# LNA.net
KiCad netlist of a schematic drawn in Altium Designer
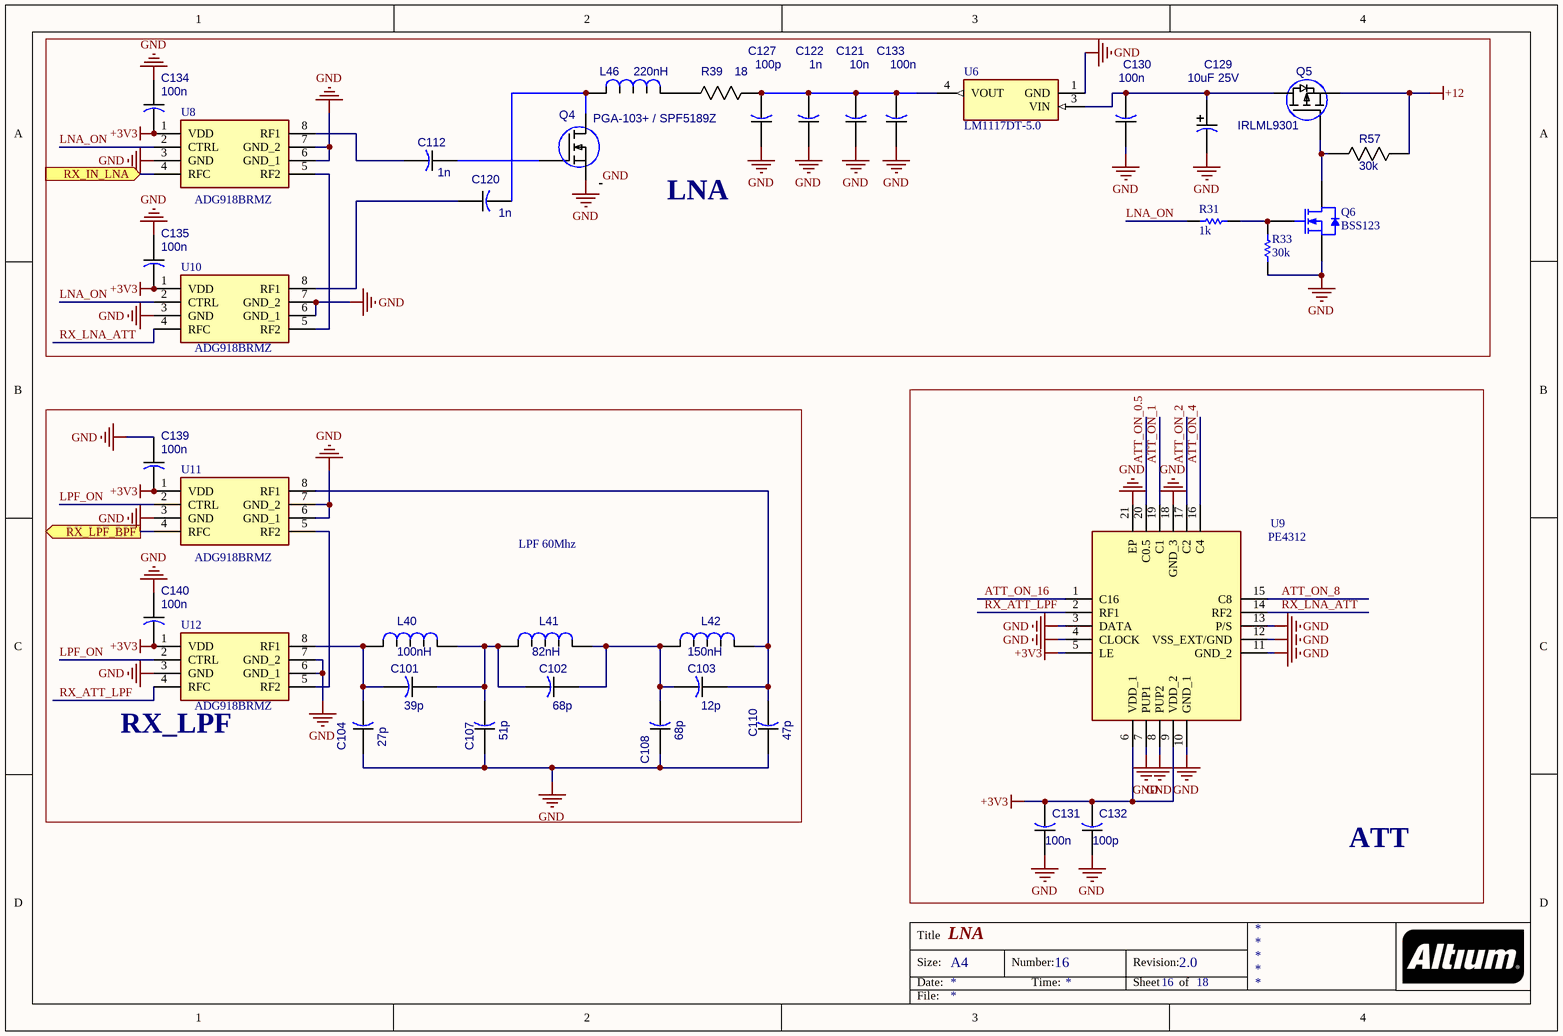
[diagram p0: LNA.SchDoc]

(export (version "E")
  (design (tool "Eeschema 10.0.6"))
  (components
    (comp (ref "C101")
      (value "39p")
      (footprint "CAP_0805")
      (description "CAP_0805")
      (libsource (lib "*") (part "CAP_0805"))
    )
    (comp (ref "C102")
      (value "68p")
      (footprint "CAP_0805")
      (description "CAP_0805")
      (libsource (lib "*") (part "CAP_0805"))
    )
    (comp (ref "C103")
      (value "12p")
      (footprint "CAP_0805")
      (description "CAP_0805")
      (libsource (lib "*") (part "CAP_0805"))
    )
    (comp (ref "C104")
      (value "27p")
      (footprint "CAP_0805")
      (description "CAP_0805")
      (libsource (lib "*") (part "CAP_0805"))
    )
    (comp (ref "C107")
      (value "51p")
      (footprint "CAP_0805")
      (description "CAP_0805")
      (libsource (lib "*") (part "CAP_0805"))
    )
    (comp (ref "C108")
      (value "68p")
      (footprint "CAP_0805")
      (description "CAP_0805")
      (libsource (lib "*") (part "CAP_0805"))
    )
    (comp (ref "C110")
      (value "47p")
      (footprint "CAP_0805")
      (description "CAP_0805")
      (libsource (lib "*") (part "CAP_0805"))
    )
    (comp (ref "C112")
      (value "1n")
      (footprint "CAP_0805")
      (description "CAP_0805")
      (libsource (lib "*") (part "CAP_0805"))
    )
    (comp (ref "C120")
      (value "1n")
      (footprint "CAP_0805")
      (description "CAP_0805")
      (libsource (lib "*") (part "CAP_0805"))
    )
    (comp (ref "C121")
      (value "10n")
      (footprint "6-0805_M")
      (description "CAP_0805")
      (libsource (lib "*") (part "CAP_0805"))
    )
    (comp (ref "C122")
      (value "1n")
      (footprint "6-0805_M")
      (description "CAP_0805")
      (libsource (lib "*") (part "CAP_0805"))
    )
    (comp (ref "C127")
      (value "100p")
      (footprint "6-0805_M")
      (description "CAP_0805")
      (libsource (lib "*") (part "CAP_0805"))
    )
    (comp (ref "C129")
      (value "10uF 25V")
      (footprint "CAPAE_5.3x5.3h6.1")
      (description "CAPAE_5.3x5.3h6.1")
      (libsource (lib "*") (part "CAPAE_5.3x5.3h6.1"))
    )
    (comp (ref "C130")
      (value "100n")
      (footprint "CAP_0805")
      (description "CAP_0805")
      (libsource (lib "") (part "CAP_0805_1"))
    )
    (comp (ref "C131")
      (value "100n")
      (footprint "6-0805_M")
      (description "CAP_0805")
      (libsource (lib "*") (part "CAP_0805"))
    )
    (comp (ref "C132")
      (value "100p")
      (footprint "6-0805_M")
      (description "CAP_0805")
      (libsource (lib "*") (part "CAP_0805"))
    )
    (comp (ref "C133")
      (value "100n")
      (footprint "CAP_0805")
      (description "CAP_0805")
      (libsource (lib "*") (part "CAP_0805"))
    )
    (comp (ref "C134")
      (value "100n")
      (footprint "CAP_0805")
      (description "CAP_0805")
      (libsource (lib "*") (part "CAP_0805"))
    )
    (comp (ref "C135")
      (value "100n")
      (footprint "CAP_0805")
      (description "CAP_0805")
      (libsource (lib "*") (part "CAP_0805"))
    )
    (comp (ref "C139")
      (value "100n")
      (footprint "CAP_0805")
      (description "CAP_0805")
      (libsource (lib "*") (part "CAP_0805"))
    )
    (comp (ref "C140")
      (value "100n")
      (footprint "CAP_0805")
      (description "CAP_0805")
      (libsource (lib "*") (part "CAP_0805"))
    )
    (comp (ref "L40")
      (value "100nH")
      (footprint "IND_0805")
      (description "IND_0805")
      (libsource (lib "*") (part "IND_0805"))
    )
    (comp (ref "L41")
      (value "82nH")
      (footprint "IND_0805")
      (description "IND_0805")
      (libsource (lib "*") (part "IND_0805"))
    )
    (comp (ref "L42")
      (value "150nH")
      (footprint "IND_0805")
      (description "IND_0805")
      (libsource (lib "*") (part "IND_0805"))
    )
    (comp (ref "L46")
      (value "220nH")
      (footprint "IND_1206")
      (description "IND_1206")
      (libsource (lib "*") (part "IND_1206"))
    )
    (comp (ref "Q4")
      (value "PGA-103+ / SPF5189Z")
      (footprint "SOT89")
      (libsource (lib "*") (part "PGA-103+"))
    )
    (comp (ref "Q5")
      (value "IRLML9301")
      (footprint "SOT23")
      (description "MOSFET")
      (libsource (lib "*") (part "MOSFET_ENH_PD"))
    )
    (comp (ref "Q6")
      (value "BSS123")
      (footprint "FAIR-SOT23-3_V")
      (fields (field (name "MANUFACTURER") "Fairchild"))
      (libsource (lib "Altium Content Vault") (part "NEMOS-GSD-3"))
    )
    (comp (ref "R31")
      (value "1k")
      (footprint "RESC2013X60X40NL20T25")
      (description "RES_0805")
      (fields (field (name "MANUFACTURER") "Panasonic") (field (name "PART NUMBER") "ERA-6AEB303V"))
      (libsource (lib "Altium Content Vault") (part "RES"))
    )
    (comp (ref "R33")
      (value "30k")
      (footprint "RESC2013X60X40NL20T25")
      (description "RES_0805")
      (fields (field (name "MANUFACTURER") "Panasonic") (field (name "PART NUMBER") "ERA-6AEB303V"))
      (libsource (lib "Altium Content Vault") (part "RES"))
    )
    (comp (ref "R39")
      (value "18")
      (footprint "RES_1206")
      (description "RES_1206")
      (libsource (lib "*") (part "RES_1206"))
    )
    (comp (ref "R57")
      (value "30k")
      (footprint "RES_0805")
      (description "RES_0805")
      (libsource (lib "*") (part "RES_0805"))
    )
    (comp (ref "U6")
      (value "LM1117DT-5.0")
      (footprint "SamacSys:TO228P991X238-3N")
      (description "Integrated Circuit")
      (fields
        (field (name "MANUFACTURER_PART_NUMBER") "LM1117DT-ADJ")
        (field (name "MOUSER PART NUMBER") "926-LM1117DT-ADJ")
      )
      (libsource (lib "*") (part "LM1117DT-ADJ"))
    )
    (comp (ref "U8")
      (value "ADG918BRMZ")
      (footprint "SamacSys:SOP65P490X110-8N")
      (description "Integrated Circuit")
      (fields (field (name "MOUSER PART NUMBER") "584-ADG918BRMZ") (field (name "RS PART NUMBER") "4969212P"))
      (libsource (lib "*") (part "ADG918BRMZ"))
    )
    (comp (ref "U9")
      (value "PE4312")
      (footprint "SamacSys:QFN50P400X400X90-21N")
      (description "Integrated Circuit")
      (fields (field (name "MANUFACTURER_PART_NUMBER") "PE4312C-Z"))
      (libsource (lib "*") (part "PE4312C-Z"))
    )
    (comp (ref "U10")
      (value "ADG918BRMZ")
      (footprint "SamacSys:SOP65P490X110-8N")
      (description "Integrated Circuit")
      (fields (field (name "MOUSER PART NUMBER") "584-ADG918BRMZ") (field (name "RS PART NUMBER") "4969212P"))
      (libsource (lib "*") (part "ADG918BRMZ"))
    )
    (comp (ref "U11")
      (value "ADG918BRMZ")
      (footprint "SamacSys:SOP65P490X110-8N")
      (description "Integrated Circuit")
      (fields (field (name "MOUSER PART NUMBER") "584-ADG918BRMZ") (field (name "RS PART NUMBER") "4969212P"))
      (libsource (lib "*") (part "ADG918BRMZ"))
    )
    (comp (ref "U12")
      (value "ADG918BRMZ")
      (footprint "SamacSys:SOP65P490X110-8N")
      (description "Integrated Circuit")
      (fields (field (name "MOUSER PART NUMBER") "584-ADG918BRMZ") (field (name "RS PART NUMBER") "4969212P"))
      (libsource (lib "*") (part "ADG918BRMZ"))
    )
  )
  (nets
    (net (code "1") (name "+3V3") (class "Default")
      (node (ref "C131") (pin "2") (pinfunction "2_2") (pintype "passive"))
      (node (ref "C132") (pin "2") (pinfunction "2_2") (pintype "passive"))
      (node (ref "C134") (pin "2") (pinfunction "2_2") (pintype "passive"))
      (node (ref "C135") (pin "2") (pinfunction "2_2") (pintype "passive"))
      (node (ref "C139") (pin "2") (pinfunction "2_2") (pintype "passive"))
      (node (ref "C140") (pin "2") (pinfunction "2_2") (pintype "passive"))
      (node (ref "U10") (pin "1") (pinfunction "VDD_1") (pintype "power_in"))
      (node (ref "U11") (pin "1") (pinfunction "VDD_1") (pintype "power_in"))
      (node (ref "U12") (pin "1") (pinfunction "VDD_1") (pintype "power_in"))
      (node (ref "U8") (pin "1") (pinfunction "VDD_1") (pintype "power_in"))
      (node (ref "U9") (pin "5") (pinfunction "LE_5") (pintype "passive"))
      (node (ref "U9") (pin "6") (pinfunction "VDD_1_6") (pintype "passive"))
      (node (ref "U9") (pin "9") (pinfunction "VDD_2_9") (pintype "passive"))
    )
    (net (code "2") (name "+12") (class "Default")
      (node (ref "Q5") (pin "2") (pinfunction "S_2") (pintype "passive"))
      (node (ref "R57") (pin "2") (pinfunction "2_2") (pintype "passive"))
    )
    (net (code "3") (name "/ATT_ON_0.5") (class "Default")
      (node (ref "U9") (pin "20") (pinfunction "C0.5_20") (pintype "passive"))
    )
    (net (code "4") (name "/ATT_ON_1") (class "Default")
      (node (ref "U9") (pin "19") (pinfunction "C1_19") (pintype "passive"))
    )
    (net (code "5") (name "/ATT_ON_2") (class "Default")
      (node (ref "U9") (pin "17") (pinfunction "C2_17") (pintype "passive"))
    )
    (net (code "6") (name "/ATT_ON_4") (class "Default")
      (node (ref "U9") (pin "16") (pinfunction "C4_16") (pintype "passive"))
    )
    (net (code "7") (name "/ATT_ON_8") (class "Default")
      (node (ref "U9") (pin "15") (pinfunction "C8_15") (pintype "passive"))
    )
    (net (code "8") (name "/ATT_ON_16") (class "Default")
      (node (ref "U9") (pin "1") (pinfunction "C16_1") (pintype "passive"))
    )
    (net (code "9") (name "/LNA_ON") (class "Default")
      (node (ref "R31") (pin "2") (pinfunction "2_2") (pintype "passive"))
      (node (ref "U10") (pin "2") (pinfunction "CTRL_2") (pintype "passive"))
      (node (ref "U8") (pin "2") (pinfunction "CTRL_2") (pintype "passive"))
    )
    (net (code "10") (name "/LPF_ON") (class "Default")
      (node (ref "U11") (pin "2") (pinfunction "CTRL_2") (pintype "passive"))
      (node (ref "U12") (pin "2") (pinfunction "CTRL_2") (pintype "passive"))
    )
    (net (code "11") (name "/RX_ATT_LPF") (class "Default")
      (node (ref "U12") (pin "4") (pinfunction "RFC_4") (pintype "passive"))
      (node (ref "U9") (pin "2") (pinfunction "RF1_2") (pintype "passive"))
    )
    (net (code "12") (name "/RX_IN_LNA") (class "Default")
      (node (ref "U8") (pin "4") (pinfunction "RFC_4") (pintype "passive"))
    )
    (net (code "13") (name "/RX_LNA_ATT") (class "Default")
      (node (ref "U10") (pin "4") (pinfunction "RFC_4") (pintype "passive"))
      (node (ref "U9") (pin "14") (pinfunction "RF2_14") (pintype "passive"))
    )
    (net (code "14") (name "/RX_LPF_BPF") (class "Default")
      (node (ref "U11") (pin "4") (pinfunction "RFC_4") (pintype "passive"))
    )
    (net (code "15") (name "GND") (class "Default")
      (node (ref "C104") (pin "1") (pinfunction "1_1") (pintype "passive"))
      (node (ref "C107") (pin "1") (pinfunction "1_1") (pintype "passive"))
      (node (ref "C108") (pin "1") (pinfunction "1_1") (pintype "passive"))
      (node (ref "C110") (pin "1") (pinfunction "1_1") (pintype "passive"))
      (node (ref "C121") (pin "1") (pinfunction "1_1") (pintype "passive"))
      (node (ref "C122") (pin "1") (pinfunction "1_1") (pintype "passive"))
      (node (ref "C127") (pin "1") (pinfunction "1_1") (pintype "passive"))
      (node (ref "C129") (pin "2") (pinfunction "MINUS_2") (pintype "passive"))
      (node (ref "C130") (pin "1") (pinfunction "1_1") (pintype "passive"))
      (node (ref "C131") (pin "1") (pinfunction "1_1") (pintype "passive"))
      (node (ref "C132") (pin "1") (pinfunction "1_1") (pintype "passive"))
      (node (ref "C133") (pin "1") (pinfunction "1_1") (pintype "passive"))
      (node (ref "C134") (pin "1") (pinfunction "1_1") (pintype "passive"))
      (node (ref "C135") (pin "1") (pinfunction "1_1") (pintype "passive"))
      (node (ref "C139") (pin "1") (pinfunction "1_1") (pintype "passive"))
      (node (ref "C140") (pin "1") (pinfunction "1_1") (pintype "passive"))
      (node (ref "Q4") (pin "0") (pinfunction "0_0") (pintype "passive"))
      (node (ref "Q4") (pin "2") (pinfunction "S_2") (pintype "passive"))
      (node (ref "Q6") (pin "2") (pinfunction "S_2") (pintype "passive"))
      (node (ref "R33") (pin "1") (pinfunction "1_1") (pintype "passive"))
      (node (ref "U10") (pin "3") (pinfunction "GND_3") (pintype "power_in"))
      (node (ref "U10") (pin "6") (pinfunction "GND_1_6") (pintype "power_in"))
      (node (ref "U10") (pin "7") (pinfunction "GND_2_7") (pintype "power_in"))
      (node (ref "U11") (pin "3") (pinfunction "GND_3") (pintype "power_in"))
      (node (ref "U11") (pin "6") (pinfunction "GND_1_6") (pintype "power_in"))
      (node (ref "U11") (pin "7") (pinfunction "GND_2_7") (pintype "power_in"))
      (node (ref "U12") (pin "3") (pinfunction "GND_3") (pintype "power_in"))
      (node (ref "U12") (pin "6") (pinfunction "GND_1_6") (pintype "power_in"))
      (node (ref "U12") (pin "7") (pinfunction "GND_2_7") (pintype "power_in"))
      (node (ref "U6") (pin "1") (pinfunction "GND_1") (pintype "passive"))
      (node (ref "U8") (pin "3") (pinfunction "GND_3") (pintype "power_in"))
      (node (ref "U8") (pin "6") (pinfunction "GND_1_6") (pintype "power_in"))
      (node (ref "U8") (pin "7") (pinfunction "GND_2_7") (pintype "power_in"))
      (node (ref "U9") (pin "10") (pinfunction "GND_1_10") (pintype "passive"))
      (node (ref "U9") (pin "11") (pinfunction "GND_2_11") (pintype "passive"))
      (node (ref "U9") (pin "12") (pinfunction "VSS_EXT/GND_12") (pintype "passive"))
      (node (ref "U9") (pin "13") (pinfunction "P/S_13") (pintype "passive"))
      (node (ref "U9") (pin "18") (pinfunction "GND_3_18") (pintype "passive"))
      (node (ref "U9") (pin "21") (pinfunction "EP_21") (pintype "passive"))
      (node (ref "U9") (pin "3") (pinfunction "DATA_3") (pintype "passive"))
      (node (ref "U9") (pin "4") (pinfunction "CLOCK_4") (pintype "passive"))
      (node (ref "U9") (pin "7") (pinfunction "PUP1_7") (pintype "passive"))
      (node (ref "U9") (pin "8") (pinfunction "PUP2_8") (pintype "passive"))
    )
    (net (code "16") (name "Net-(C101-Pad1)") (class "Default")
      (node (ref "C101") (pin "1") (pinfunction "1_1") (pintype "passive"))
      (node (ref "C102") (pin "2") (pinfunction "2_2") (pintype "passive"))
      (node (ref "C107") (pin "2") (pinfunction "2_2") (pintype "passive"))
      (node (ref "L40") (pin "2") (pinfunction "2_2") (pintype "passive"))
      (node (ref "L41") (pin "1") (pinfunction "1_1") (pintype "passive"))
    )
    (net (code "17") (name "Net-(C102-Pad1)") (class "Default")
      (node (ref "C102") (pin "1") (pinfunction "1_1") (pintype "passive"))
      (node (ref "C103") (pin "2") (pinfunction "2_2") (pintype "passive"))
      (node (ref "C108") (pin "2") (pinfunction "2_2") (pintype "passive"))
      (node (ref "L41") (pin "2") (pinfunction "2_2") (pintype "passive"))
      (node (ref "L42") (pin "1") (pinfunction "1_1") (pintype "passive"))
    )
    (net (code "18") (name "Net-(C129-PLUS)") (class "Default")
      (node (ref "C129") (pin "1") (pinfunction "PLUS_1") (pintype "passive"))
      (node (ref "C130") (pin "2") (pinfunction "2_2") (pintype "passive"))
      (node (ref "Q5") (pin "3") (pinfunction "D_3") (pintype "passive"))
      (node (ref "U6") (pin "3") (pinfunction "VIN_3") (pintype "input"))
    )
    (net (code "19") (name "Net-(L46-1)") (class "Default")
      (node (ref "C120") (pin "2") (pinfunction "2_2") (pintype "passive"))
      (node (ref "L46") (pin "2") (pinfunction "1_2") (pintype "passive"))
      (node (ref "Q4") (pin "3") (pinfunction "D_3") (pintype "passive"))
    )
    (net (code "20") (name "Net-(L46-2)") (class "Default")
      (node (ref "L46") (pin "1") (pinfunction "2_1") (pintype "passive"))
      (node (ref "R39") (pin "2") (pinfunction "2_2") (pintype "passive"))
    )
    (net (code "21") (name "Net-(Q4-G)") (class "Default")
      (node (ref "C112") (pin "1") (pinfunction "1_1") (pintype "passive"))
      (node (ref "Q4") (pin "1") (pinfunction "G_1") (pintype "passive"))
    )
    (net (code "22") (name "Net-(Q5-G)") (class "Default")
      (node (ref "Q5") (pin "1") (pinfunction "G_1") (pintype "passive"))
      (node (ref "Q6") (pin "3") (pinfunction "D_3") (pintype "passive"))
      (node (ref "R57") (pin "1") (pinfunction "1_1") (pintype "passive"))
    )
    (net (code "23") (name "Net-(Q6-G)") (class "Default")
      (node (ref "Q6") (pin "1") (pinfunction "G_1") (pintype "passive"))
      (node (ref "R31") (pin "1") (pinfunction "1_1") (pintype "passive"))
      (node (ref "R33") (pin "2") (pinfunction "2_2") (pintype "passive"))
    )
    (net (code "24") (name "Net-(U6-VOUT)") (class "Default")
      (node (ref "C121") (pin "2") (pinfunction "2_2") (pintype "passive"))
      (node (ref "C122") (pin "2") (pinfunction "2_2") (pintype "passive"))
      (node (ref "C127") (pin "2") (pinfunction "2_2") (pintype "passive"))
      (node (ref "C133") (pin "2") (pinfunction "2_2") (pintype "passive"))
      (node (ref "R39") (pin "1") (pinfunction "1_1") (pintype "passive"))
      (node (ref "U6") (pin "4") (pinfunction "VOUT_4") (pintype "output"))
    )
    (net (code "25") (name "Net-(U8-RF1)") (class "Default")
      (node (ref "C112") (pin "2") (pinfunction "2_2") (pintype "passive"))
      (node (ref "U8") (pin "8") (pinfunction "RF1_8") (pintype "passive"))
    )
    (net (code "26") (name "Net-(U10-RF1)") (class "Default")
      (node (ref "C120") (pin "1") (pinfunction "1_1") (pintype "passive"))
      (node (ref "U10") (pin "8") (pinfunction "RF1_8") (pintype "passive"))
    )
    (net (code "27") (name "Net-(U10-RF2)") (class "Default")
      (node (ref "U10") (pin "5") (pinfunction "RF2_5") (pintype "passive"))
      (node (ref "U8") (pin "5") (pinfunction "RF2_5") (pintype "passive"))
    )
    (net (code "28") (name "Net-(U11-RF1)") (class "Default")
      (node (ref "C103") (pin "1") (pinfunction "1_1") (pintype "passive"))
      (node (ref "C110") (pin "2") (pinfunction "2_2") (pintype "passive"))
      (node (ref "L42") (pin "2") (pinfunction "2_2") (pintype "passive"))
      (node (ref "U11") (pin "8") (pinfunction "RF1_8") (pintype "passive"))
    )
    (net (code "29") (name "Net-(U11-RF2)") (class "Default")
      (node (ref "U11") (pin "5") (pinfunction "RF2_5") (pintype "passive"))
      (node (ref "U12") (pin "5") (pinfunction "RF2_5") (pintype "passive"))
    )
    (net (code "30") (name "Net-(U12-RF1)") (class "Default")
      (node (ref "C101") (pin "2") (pinfunction "2_2") (pintype "passive"))
      (node (ref "C104") (pin "2") (pinfunction "2_2") (pintype "passive"))
      (node (ref "L40") (pin "1") (pinfunction "1_1") (pintype "passive"))
      (node (ref "U12") (pin "8") (pinfunction "RF1_8") (pintype "passive"))
    )
  )
)
